# SCH_Line_Following_Robot_PCB_PlanA.net
KiCad netlist of a schematic drawn in EasyEDA
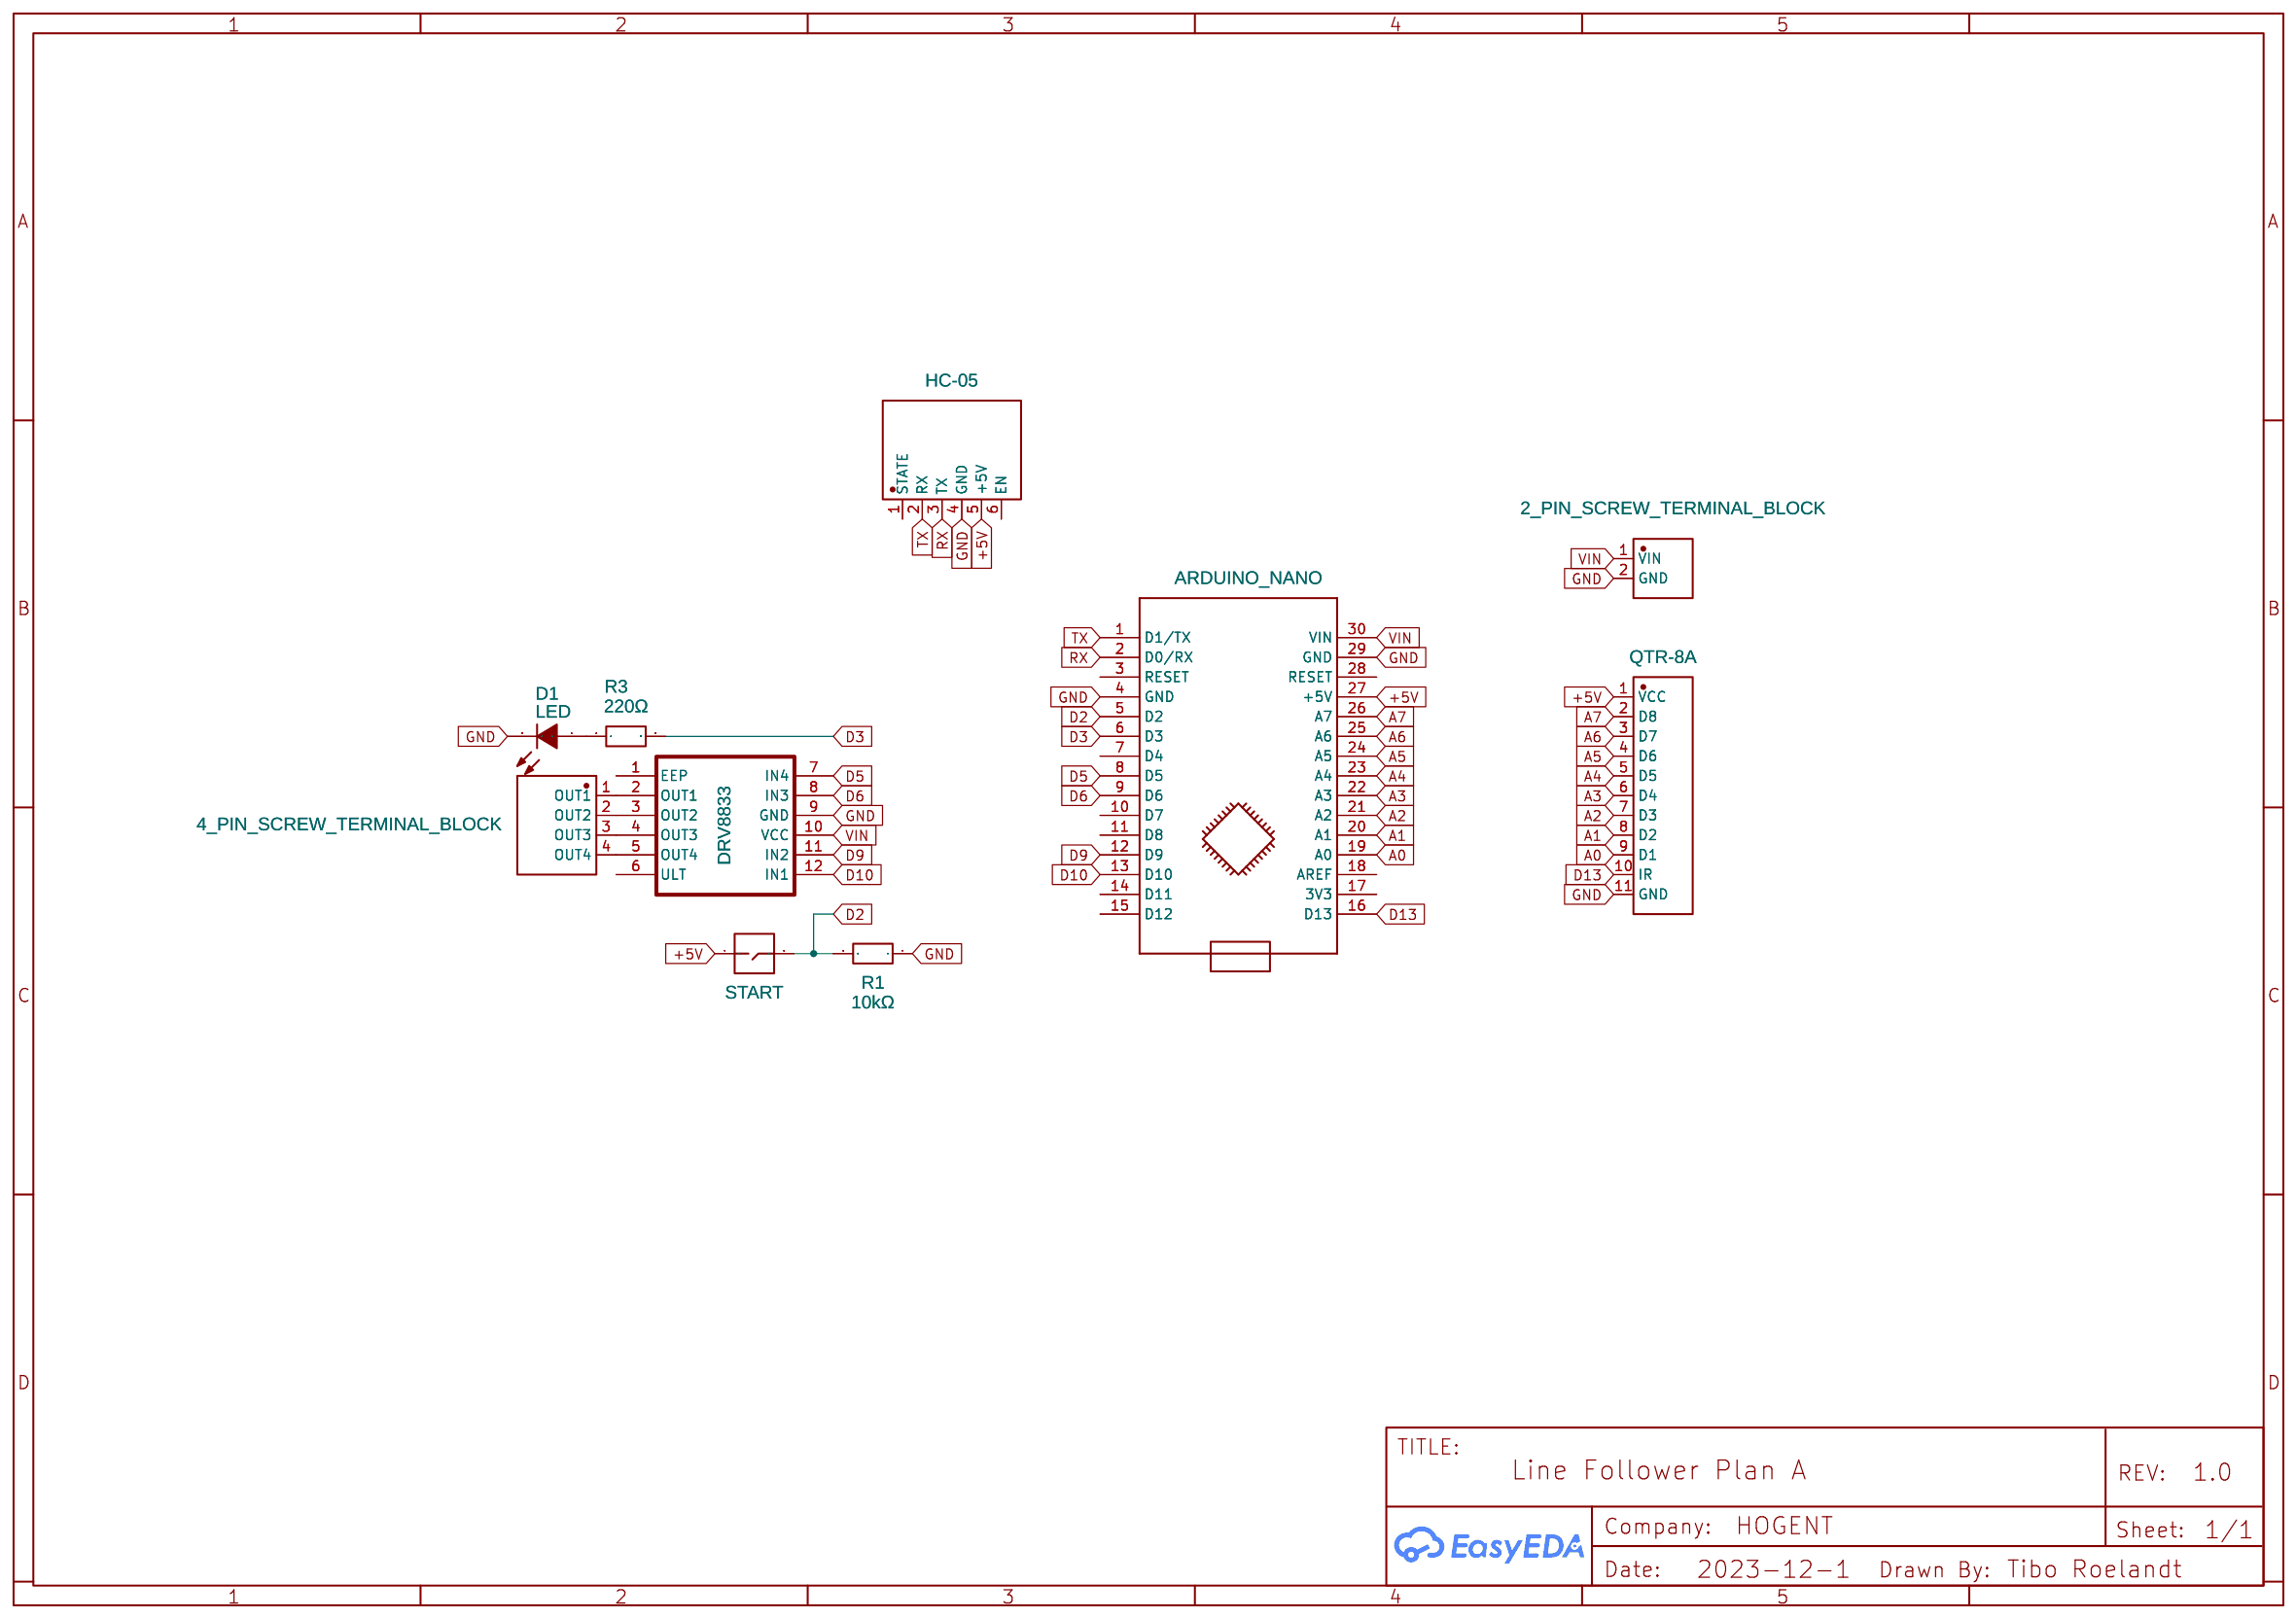
[diagram p0: schematic sheet]

(export (version "E")
  (design (tool "Eeschema 10.0.6"))
  (components
    (comp (ref "2_PIN_SCREW_TERMINAL_BLOCK")
      (value "2 Pin Screw Terminal Block Connector 2.54 mm")
      (libsource (lib "") (part "2 PIN SCREW TERMINAL BLOCK CONNECTOR 2.54 MM"))
    )
    (comp (ref "4_PIN_SCREW_TERMINAL_BLOCK")
      (value "4 PIN SCREW TERMINAL BLOCK CONNECTOR 2.54 MM")
      (libsource (lib "") (part "4 PIN SCREW TERMINAL BLOCK CONNECTOR 2.54 MM"))
    )
    (comp (ref "ARDUINO_NANO")
      (value "ARDUINO NANO CLOCK")
      (fields (field (name "Manufacturer Part") "Arduino-NANO"))
      (libsource (lib "") (part "ARDUINO NANO CLOCK"))
    )
    (comp (ref "D1")
      (value "LED")
      (fields (field (name "Manufacturer Part") "5600") (field (name "Manufacturer") "VccLite"))
      (libsource (lib "") (part "LED"))
    )
    (comp (ref "DRV8833") (value "DRV8833") (libsource (lib "") (part "DRV8833 12PIN")))
    (comp (ref "HC-05") (value "HC-05") (libsource (lib "") (part "HC-05")))
    (comp (ref "QTR-8A") (value "QTR-8A") (libsource (lib "") (part "QTR-8A")))
    (comp (ref "R1")
      (value "10kΩ")
      (libsource (lib "") (part "AXIAL RESISTOR 220 OHM - TH_BD2.3-L6.0-P10.00-D0.4"))
    )
    (comp (ref "R3")
      (value "220Ω")
      (libsource (lib "") (part "AXIAL RESISTOR 220 OHM - TH_BD2.3-L6.0-P10.00-D0.4_1"))
    )
    (comp (ref "START") (value "start") (libsource (lib "") (part "Push Button")))
  )
  (nets
    (net (code "1") (name "+5V") (class "Default")
      (node (ref "ARDUINO_NANO") (pin "27") (pinfunction "+5V_27") (pintype "unspecified"))
      (node (ref "HC-05") (pin "5") (pinfunction "+5V_5") (pintype "unspecified"))
      (node (ref "QTR-8A") (pin "1") (pinfunction "VCC_1") (pintype "unspecified"))
      (node (ref "START") (pin "1") (pinfunction "1_1") (pintype "unspecified"))
    )
    (net (code "2") (name "A0") (class "Default")
      (node (ref "ARDUINO_NANO") (pin "19") (pinfunction "A0_19") (pintype "unspecified"))
      (node (ref "QTR-8A") (pin "9") (pinfunction "D1_9") (pintype "unspecified"))
    )
    (net (code "3") (name "A1") (class "Default")
      (node (ref "ARDUINO_NANO") (pin "20") (pinfunction "A1_20") (pintype "unspecified"))
      (node (ref "QTR-8A") (pin "8") (pinfunction "D2_8") (pintype "unspecified"))
    )
    (net (code "4") (name "A2") (class "Default")
      (node (ref "ARDUINO_NANO") (pin "21") (pinfunction "A2_21") (pintype "unspecified"))
      (node (ref "QTR-8A") (pin "7") (pinfunction "D3_7") (pintype "unspecified"))
    )
    (net (code "5") (name "A3") (class "Default")
      (node (ref "ARDUINO_NANO") (pin "22") (pinfunction "A3_22") (pintype "unspecified"))
      (node (ref "QTR-8A") (pin "6") (pinfunction "D4_6") (pintype "unspecified"))
    )
    (net (code "6") (name "A4") (class "Default")
      (node (ref "ARDUINO_NANO") (pin "23") (pinfunction "A4_23") (pintype "unspecified"))
      (node (ref "QTR-8A") (pin "5") (pinfunction "D5_5") (pintype "unspecified"))
    )
    (net (code "7") (name "A5") (class "Default")
      (node (ref "ARDUINO_NANO") (pin "24") (pinfunction "A5_24") (pintype "unspecified"))
      (node (ref "QTR-8A") (pin "4") (pinfunction "D6_4") (pintype "unspecified"))
    )
    (net (code "8") (name "A6") (class "Default")
      (node (ref "ARDUINO_NANO") (pin "25") (pinfunction "A6_25") (pintype "unspecified"))
      (node (ref "QTR-8A") (pin "3") (pinfunction "D7_3") (pintype "unspecified"))
    )
    (net (code "9") (name "A7") (class "Default")
      (node (ref "ARDUINO_NANO") (pin "26") (pinfunction "A7_26") (pintype "unspecified"))
      (node (ref "QTR-8A") (pin "2") (pinfunction "D8_2") (pintype "unspecified"))
    )
    (net (code "10") (name "D2") (class "Default")
      (node (ref "ARDUINO_NANO") (pin "5") (pinfunction "D2_5") (pintype "unspecified"))
      (node (ref "R1") (pin "2") (pinfunction "2_2") (pintype "unspecified"))
      (node (ref "START") (pin "2") (pinfunction "2_2") (pintype "unspecified"))
    )
    (net (code "11") (name "D3") (class "Default")
      (node (ref "ARDUINO_NANO") (pin "6") (pinfunction "D3_6") (pintype "unspecified"))
      (node (ref "R3") (pin "2") (pinfunction "2_2") (pintype "unspecified"))
    )
    (net (code "12") (name "D5") (class "Default")
      (node (ref "ARDUINO_NANO") (pin "8") (pinfunction "D5_8") (pintype "unspecified"))
      (node (ref "DRV8833") (pin "7") (pinfunction "IN4_7") (pintype "unspecified"))
    )
    (net (code "13") (name "D6") (class "Default")
      (node (ref "ARDUINO_NANO") (pin "9") (pinfunction "D6_9") (pintype "unspecified"))
      (node (ref "DRV8833") (pin "8") (pinfunction "IN3_8") (pintype "unspecified"))
    )
    (net (code "14") (name "D9") (class "Default")
      (node (ref "ARDUINO_NANO") (pin "12") (pinfunction "D9_12") (pintype "unspecified"))
      (node (ref "DRV8833") (pin "11") (pinfunction "IN2_11") (pintype "unspecified"))
    )
    (net (code "15") (name "D10") (class "Default")
      (node (ref "ARDUINO_NANO") (pin "13") (pinfunction "D10_13") (pintype "unspecified"))
      (node (ref "DRV8833") (pin "12") (pinfunction "IN1_12") (pintype "unspecified"))
    )
    (net (code "16") (name "D13") (class "Default")
      (node (ref "ARDUINO_NANO") (pin "16") (pinfunction "D13_16") (pintype "unspecified"))
      (node (ref "QTR-8A") (pin "10") (pinfunction "IR_10") (pintype "unspecified"))
    )
    (net (code "17") (name "GND") (class "Default")
      (node (ref "2_PIN_SCREW_TERMINAL_BLOCK") (pin "2") (pinfunction "GND_2") (pintype "unspecified"))
      (node (ref "ARDUINO_NANO") (pin "29") (pinfunction "GND_29") (pintype "unspecified"))
      (node (ref "ARDUINO_NANO") (pin "4") (pinfunction "GND_4") (pintype "unspecified"))
      (node (ref "D1") (pin "2") (pinfunction "K_2") (pintype "unspecified"))
      (node (ref "DRV8833") (pin "9") (pinfunction "GND_9") (pintype "unspecified"))
      (node (ref "HC-05") (pin "4") (pinfunction "GND_4") (pintype "unspecified"))
      (node (ref "QTR-8A") (pin "11") (pinfunction "GND_11") (pintype "unspecified"))
      (node (ref "R1") (pin "1") (pinfunction "1_1") (pintype "unspecified"))
    )
    (net (code "18") (name "Net-(4_PIN_SCREW_TERMINAL_BLOCK-OUT1)") (class "Default")
      (node (ref "4_PIN_SCREW_TERMINAL_BLOCK") (pin "1") (pinfunction "OUT1_1") (pintype "unspecified"))
      (node (ref "DRV8833") (pin "2") (pinfunction "OUT1_2") (pintype "unspecified"))
    )
    (net (code "19") (name "Net-(4_PIN_SCREW_TERMINAL_BLOCK-OUT2)") (class "Default")
      (node (ref "4_PIN_SCREW_TERMINAL_BLOCK") (pin "2") (pinfunction "OUT2_2") (pintype "unspecified"))
      (node (ref "DRV8833") (pin "3") (pinfunction "OUT2_3") (pintype "unspecified"))
    )
    (net (code "20") (name "Net-(4_PIN_SCREW_TERMINAL_BLOCK-OUT3)") (class "Default")
      (node (ref "4_PIN_SCREW_TERMINAL_BLOCK") (pin "3") (pinfunction "OUT3_3") (pintype "unspecified"))
      (node (ref "DRV8833") (pin "4") (pinfunction "OUT3_4") (pintype "unspecified"))
    )
    (net (code "21") (name "Net-(4_PIN_SCREW_TERMINAL_BLOCK-OUT4)") (class "Default")
      (node (ref "4_PIN_SCREW_TERMINAL_BLOCK") (pin "4") (pinfunction "OUT4_4") (pintype "unspecified"))
      (node (ref "DRV8833") (pin "5") (pinfunction "OUT4_5") (pintype "unspecified"))
    )
    (net (code "22") (name "Net-(D1-A)") (class "Default")
      (node (ref "D1") (pin "1") (pinfunction "A_1") (pintype "unspecified"))
      (node (ref "R3") (pin "1") (pinfunction "1_1") (pintype "unspecified"))
    )
    (net (code "23") (name "RX") (class "Default")
      (node (ref "ARDUINO_NANO") (pin "2") (pinfunction "D0/RX_2") (pintype "unspecified"))
      (node (ref "HC-05") (pin "3") (pinfunction "TX_3") (pintype "unspecified"))
    )
    (net (code "24") (name "TX") (class "Default")
      (node (ref "ARDUINO_NANO") (pin "1") (pinfunction "D1/TX_1") (pintype "unspecified"))
      (node (ref "HC-05") (pin "2") (pinfunction "RX_2") (pintype "unspecified"))
    )
    (net (code "25") (name "VIN") (class "Default")
      (node (ref "2_PIN_SCREW_TERMINAL_BLOCK") (pin "1") (pinfunction "VIN_1") (pintype "unspecified"))
      (node (ref "ARDUINO_NANO") (pin "30") (pinfunction "VIN_30") (pintype "unspecified"))
      (node (ref "DRV8833") (pin "10") (pinfunction "VCC_10") (pintype "unspecified"))
    )
    (net (code "26") (name "unconnected-(ARDUINO_NANO-3V3-Pad17)") (class "Default")
      (node (ref "ARDUINO_NANO") (pin "17") (pinfunction "3V3_17") (pintype "unspecified"))
    )
    (net (code "27") (name "unconnected-(ARDUINO_NANO-AREF-Pad18)") (class "Default")
      (node (ref "ARDUINO_NANO") (pin "18") (pinfunction "AREF_18") (pintype "unspecified"))
    )
    (net (code "28") (name "unconnected-(ARDUINO_NANO-D4-Pad7)") (class "Default")
      (node (ref "ARDUINO_NANO") (pin "7") (pinfunction "D4_7") (pintype "unspecified"))
    )
    (net (code "29") (name "unconnected-(ARDUINO_NANO-D7-Pad10)") (class "Default")
      (node (ref "ARDUINO_NANO") (pin "10") (pinfunction "D7_10") (pintype "unspecified"))
    )
    (net (code "30") (name "unconnected-(ARDUINO_NANO-D8-Pad11)") (class "Default")
      (node (ref "ARDUINO_NANO") (pin "11") (pinfunction "D8_11") (pintype "unspecified"))
    )
    (net (code "31") (name "unconnected-(ARDUINO_NANO-D11-Pad14)") (class "Default")
      (node (ref "ARDUINO_NANO") (pin "14") (pinfunction "D11_14") (pintype "unspecified"))
    )
    (net (code "32") (name "unconnected-(ARDUINO_NANO-D12-Pad15)") (class "Default")
      (node (ref "ARDUINO_NANO") (pin "15") (pinfunction "D12_15") (pintype "unspecified"))
    )
    (net (code "33") (name "unconnected-(ARDUINO_NANO-RESET-Pad3)") (class "Default")
      (node (ref "ARDUINO_NANO") (pin "3") (pinfunction "RESET_3") (pintype "unspecified"))
    )
    (net (code "34") (name "unconnected-(ARDUINO_NANO-RESET-Pad28)") (class "Default")
      (node (ref "ARDUINO_NANO") (pin "28") (pinfunction "RESET_28") (pintype "unspecified"))
    )
    (net (code "35") (name "unconnected-(DRV8833-EEP-Pad1)") (class "Default")
      (node (ref "DRV8833") (pin "1") (pinfunction "EEP_1") (pintype "unspecified"))
    )
    (net (code "36") (name "unconnected-(DRV8833-ULT-Pad6)") (class "Default")
      (node (ref "DRV8833") (pin "6") (pinfunction "ULT_6") (pintype "unspecified"))
    )
    (net (code "37") (name "unconnected-(HC-05-EN-Pad6)") (class "Default")
      (node (ref "HC-05") (pin "6") (pinfunction "EN_6") (pintype "unspecified"))
    )
    (net (code "38") (name "unconnected-(HC-05-STATE-Pad1)") (class "Default")
      (node (ref "HC-05") (pin "1") (pinfunction "STATE_1") (pintype "unspecified"))
    )
  )
)
